# Multivibrator.net
KiCad netlist of a schematic drawn in Altium Designer
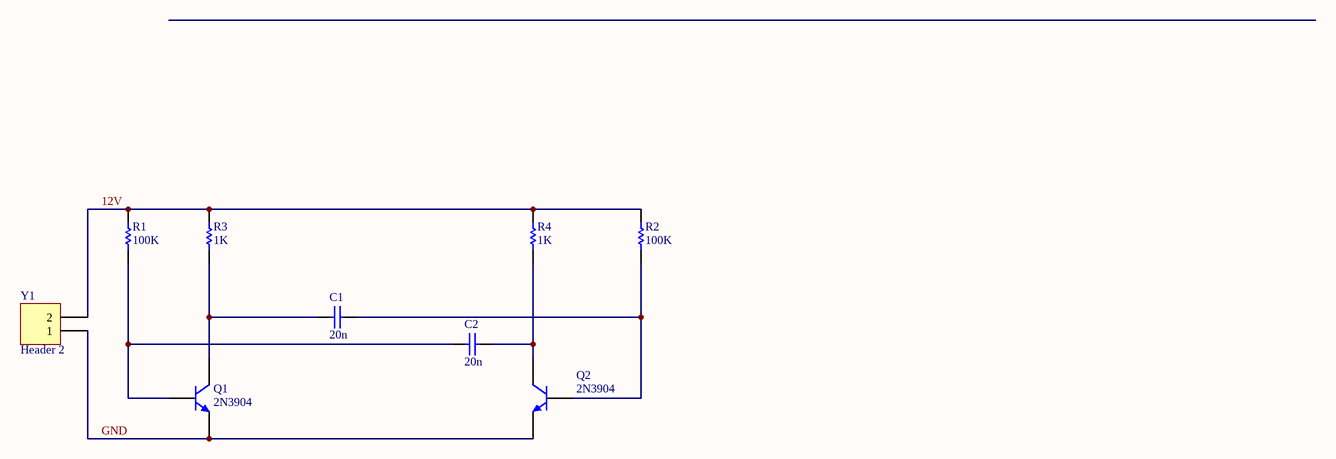
[diagram p0: Multivibrator.SchDoc]

(export (version "E")
  (design (tool "Eeschema 10.0.6"))
  (components
    (comp (ref "C1")
      (value "20n")
      (footprint "RAD-0.3")
      (description "Capacitor")
      (fields (field (name "PUBLISHER") "Altium Limited"))
      (libsource (lib "Miscellaneous Devices") (part "Cap"))
    )
    (comp (ref "C2")
      (value "20n")
      (footprint "RAD-0.3")
      (description "Capacitor")
      (fields (field (name "PUBLISHER") "Altium Limited"))
      (libsource (lib "Miscellaneous Devices") (part "Cap"))
    )
    (comp (ref "Q1")
      (value "2N3904")
      (footprint "TO-92A")
      (description "NPN General Purpose Amplifier")
      (fields (field (name "PUBLISHER") "Altium Limited"))
      (libsource (lib "Miscellaneous Devices") (part "2N3904"))
    )
    (comp (ref "Q2")
      (value "2N3904")
      (footprint "TO-92A")
      (description "NPN General Purpose Amplifier")
      (fields (field (name "PUBLISHER") "Altium Limited"))
      (libsource (lib "Miscellaneous Devices") (part "2N3904"))
    )
    (comp (ref "R1")
      (value "100K")
      (footprint "AXIAL-0.3")
      (description "Resistor")
      (fields (field (name "PUBLISHER") "Altium Limited"))
      (libsource (lib "Miscellaneous Devices") (part "Res1"))
    )
    (comp (ref "R2")
      (value "100K")
      (footprint "AXIAL-0.3")
      (description "Resistor")
      (fields (field (name "PUBLISHER") "Altium Limited"))
      (libsource (lib "Miscellaneous Devices") (part "Res1"))
    )
    (comp (ref "R3")
      (value "1K")
      (footprint "AXIAL-0.3")
      (description "Resistor")
      (fields (field (name "PUBLISHER") "Altium Limited"))
      (libsource (lib "Miscellaneous Devices") (part "Res1"))
    )
    (comp (ref "R4")
      (value "1K")
      (footprint "AXIAL-0.3")
      (description "Resistor")
      (fields (field (name "PUBLISHER") "Altium Limited"))
      (libsource (lib "Miscellaneous Devices") (part "Res1"))
    )
    (comp (ref "Y1")
      (value "Header 2")
      (footprint "HDR1X2")
      (description "Header, 2-Pin")
      (fields (field (name "PUBLISHER") "Altium Limited"))
      (libsource (lib "Miscellaneous Connectors") (part "Header 2"))
    )
  )
  (nets
    (net (code "1") (name "/12V") (class "Default")
      (node (ref "R1") (pin "2") (pinfunction "2_2") (pintype "passive"))
      (node (ref "R2") (pin "2") (pinfunction "2_2") (pintype "passive"))
      (node (ref "R3") (pin "2") (pinfunction "2_2") (pintype "passive"))
      (node (ref "R4") (pin "2") (pinfunction "2_2") (pintype "passive"))
      (node (ref "Y1") (pin "2") (pinfunction "2_2") (pintype "passive"))
    )
    (net (code "2") (name "/GND") (class "Default")
      (node (ref "Q1") (pin "1") (pinfunction "E_1") (pintype "passive"))
      (node (ref "Q2") (pin "1") (pinfunction "E_1") (pintype "passive"))
      (node (ref "Y1") (pin "1") (pinfunction "1_1") (pintype "passive"))
    )
    (net (code "3") (name "Net-(Q1-B)") (class "Default")
      (node (ref "C2") (pin "1") (pinfunction "1_1") (pintype "passive"))
      (node (ref "Q1") (pin "2") (pinfunction "B_2") (pintype "passive"))
      (node (ref "R1") (pin "1") (pinfunction "1_1") (pintype "passive"))
    )
    (net (code "4") (name "Net-(Q1-C)") (class "Default")
      (node (ref "C1") (pin "1") (pinfunction "1_1") (pintype "passive"))
      (node (ref "Q1") (pin "3") (pinfunction "C_3") (pintype "passive"))
      (node (ref "R3") (pin "1") (pinfunction "1_1") (pintype "passive"))
    )
    (net (code "5") (name "Net-(Q2-B)") (class "Default")
      (node (ref "C1") (pin "2") (pinfunction "2_2") (pintype "passive"))
      (node (ref "Q2") (pin "2") (pinfunction "B_2") (pintype "passive"))
      (node (ref "R2") (pin "1") (pinfunction "1_1") (pintype "passive"))
    )
    (net (code "6") (name "Net-(Q2-C)") (class "Default")
      (node (ref "C2") (pin "2") (pinfunction "2_2") (pintype "passive"))
      (node (ref "Q2") (pin "3") (pinfunction "C_3") (pintype "passive"))
      (node (ref "R4") (pin "1") (pinfunction "1_1") (pintype "passive"))
    )
  )
)
